# JoyDivision.net
KiCad netlist of a schematic drawn in EAGLE
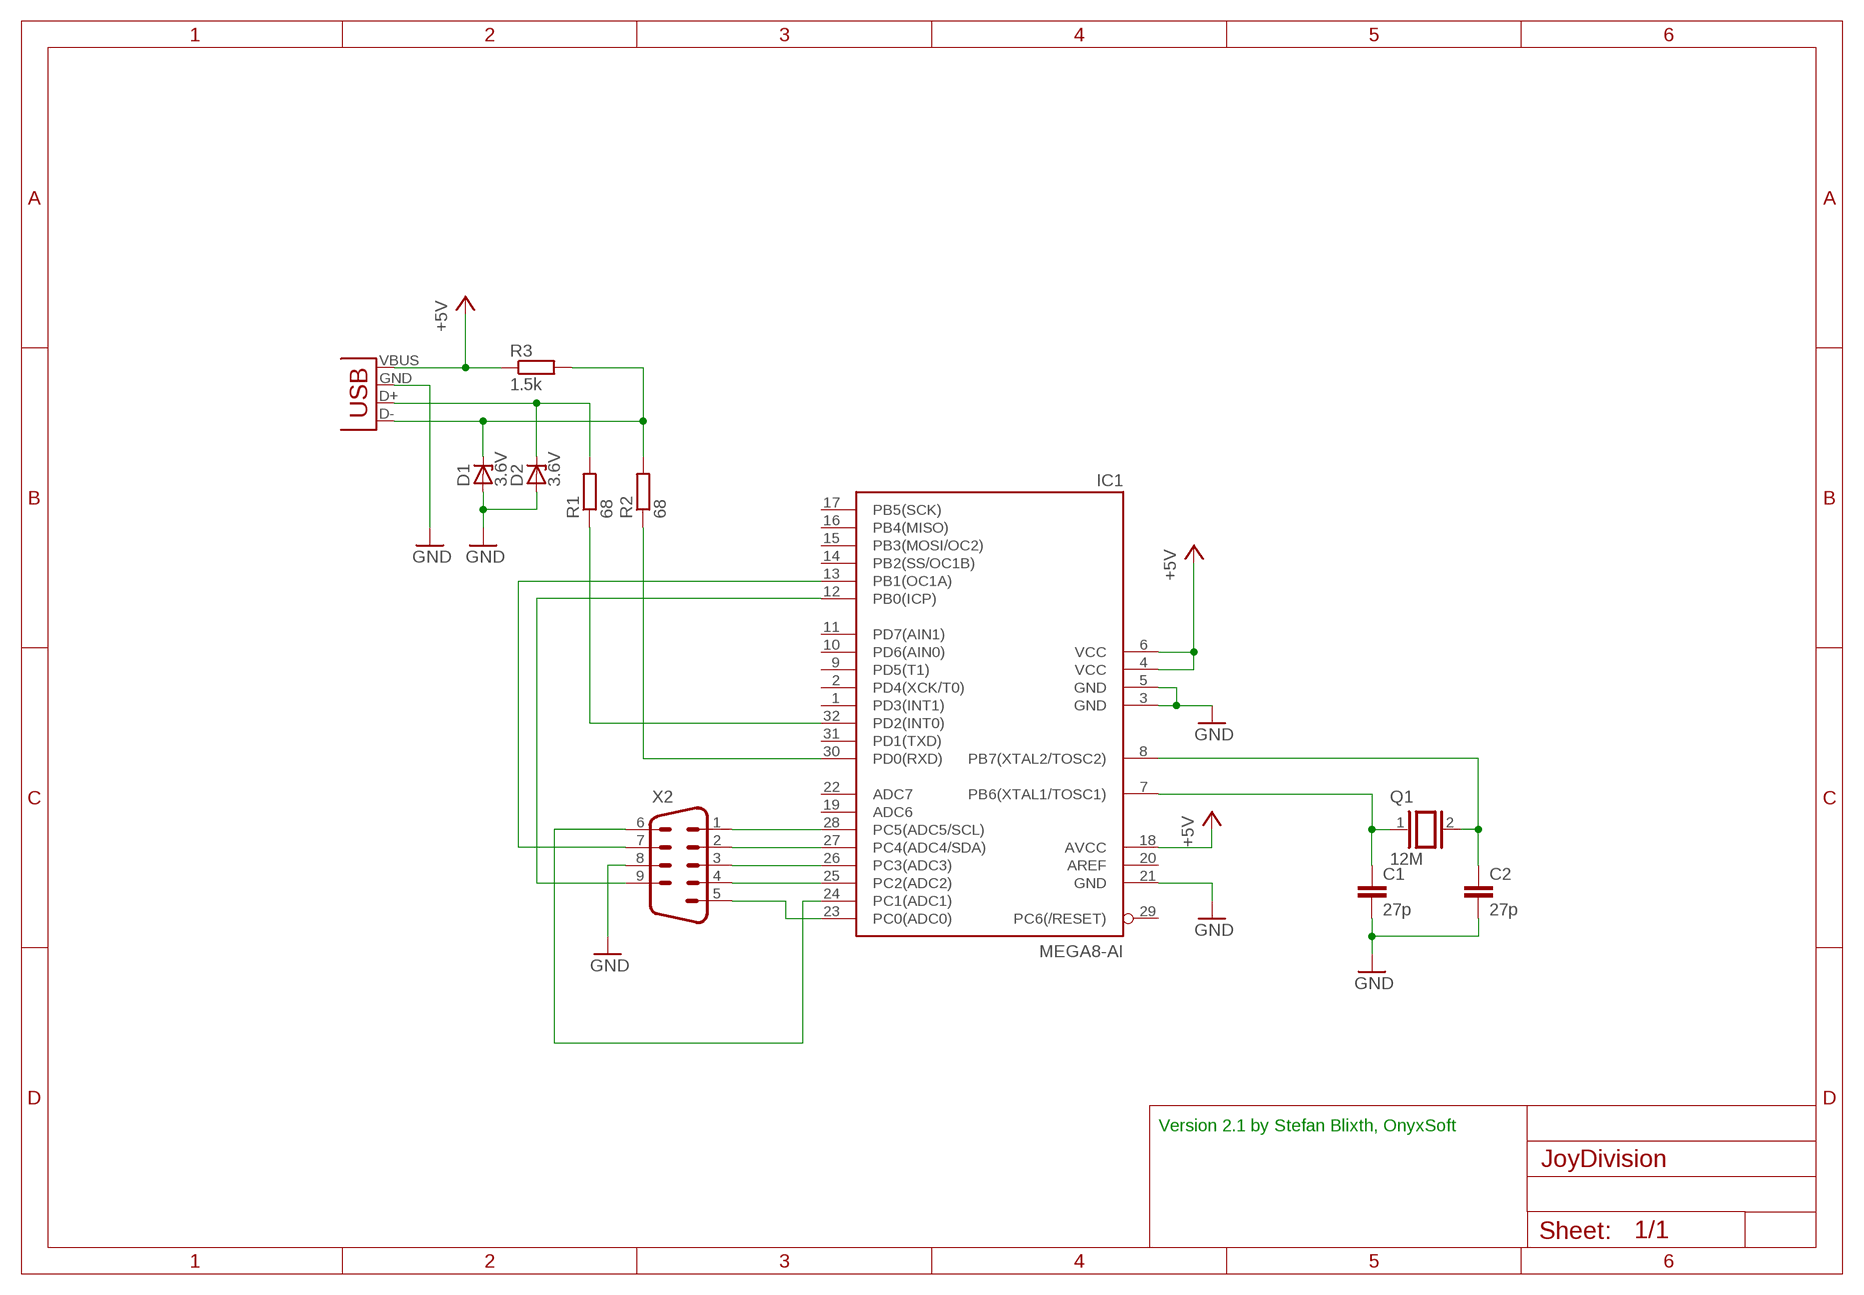
[diagram p0: schematic, sheet 1]

(export (version "E")
  (design (tool "Eeschema 10.0.6"))
  (components
    (comp (ref "C1")
      (value "27p")
      (footprint "eagle-import:C0805")
      (libsource (lib "eagle-import") (part "C-EUC0805"))
    )
    (comp (ref "C2")
      (value "27p")
      (footprint "eagle-import:C0805")
      (libsource (lib "eagle-import") (part "C-EUC0805"))
    )
    (comp (ref "D1")
      (value "3.6V")
      (footprint "eagle-import:SOD80C")
      (libsource (lib "eagle-import") (part "ZENER-DIODESOD80C"))
    )
    (comp (ref "D2")
      (value "3.6V")
      (footprint "eagle-import:SOD80C")
      (libsource (lib "eagle-import") (part "ZENER-DIODESOD80C"))
    )
    (comp (ref "IC1")
      (value "MEGA8-AI")
      (footprint "eagle-import:TQFP32-08")
      (fields (field (name "MPN") "ATMEGA8-16AU"))
      (libsource (lib "eagle-import") (part "MEGA8-AI"))
    )
    (comp (ref "JP1")
      (value "USB-A-H")
      (footprint "eagle-import:USB-A-H")
      (libsource (lib "eagle-import") (part "USB-A-H"))
    )
    (comp (ref "Q1")
      (value "12M")
      (footprint "eagle-import:QS")
      (libsource (lib "eagle-import") (part "XTAL/S"))
    )
    (comp (ref "R1")
      (value "68")
      (footprint "eagle-import:M0805")
      (libsource (lib "eagle-import") (part "R-EU_M0805"))
    )
    (comp (ref "R2")
      (value "68")
      (footprint "eagle-import:M0805")
      (libsource (lib "eagle-import") (part "R-EU_M0805"))
    )
    (comp (ref "R3")
      (value "1.5k")
      (footprint "eagle-import:M0805")
      (libsource (lib "eagle-import") (part "R-EU_M0805"))
    )
    (comp (ref "X2")
      (value "M09D")
      (footprint "eagle-import:M09D")
      (libsource (lib "eagle-import") (part "M09D"))
    )
  )
  (nets
    (net (code "1") (name "+5V") (class "Default")
      (node (ref "IC1") (pin "18") (pinfunction "AVCC_18") (pintype "power_in"))
      (node (ref "IC1") (pin "4") (pinfunction "VCC_4") (pintype "power_in"))
      (node (ref "IC1") (pin "6") (pinfunction "VCC_6") (pintype "power_in"))
      (node (ref "JP1") (pin "VBUS") (pinfunction "GND_VBUS") (pintype "bidirectional"))
      (node (ref "R3") (pin "1") (pinfunction "1_1") (pintype "passive"))
    )
    (net (code "2") (name "GND") (class "Default")
      (node (ref "C1") (pin "2") (pinfunction "2_2") (pintype "passive"))
      (node (ref "C2") (pin "2") (pinfunction "2_2") (pintype "passive"))
      (node (ref "D1") (pin "A") (pinfunction "A_A") (pintype "passive"))
      (node (ref "D2") (pin "A") (pinfunction "A_A") (pintype "passive"))
      (node (ref "IC1") (pin "21") (pinfunction "GND_21") (pintype "power_in"))
      (node (ref "IC1") (pin "3") (pinfunction "GND_3") (pintype "power_in"))
      (node (ref "IC1") (pin "5") (pinfunction "GND_5") (pintype "power_in"))
      (node (ref "JP1") (pin "GND") (pinfunction "VBUS_GND") (pintype "bidirectional"))
      (node (ref "X2") (pin "8") (pinfunction "8_8") (pintype "passive"))
    )
    (net (code "3") (name "Net-(IC1-PB0(ICP))") (class "Default")
      (node (ref "IC1") (pin "12") (pinfunction "PB0(ICP)_12") (pintype "bidirectional"))
      (node (ref "X2") (pin "9") (pinfunction "9_9") (pintype "passive"))
    )
    (net (code "4") (name "Net-(IC1-PB1(OC1A))") (class "Default")
      (node (ref "IC1") (pin "13") (pinfunction "PB1(OC1A)_13") (pintype "bidirectional"))
      (node (ref "X2") (pin "7") (pinfunction "7_7") (pintype "passive"))
    )
    (net (code "5") (name "Net-(IC1-PB6(XTAL1{slash}TOSC1))") (class "Default")
      (node (ref "C1") (pin "1") (pinfunction "1_1") (pintype "passive"))
      (node (ref "IC1") (pin "7") (pinfunction "PB6(XTAL1/TOSC1)_7") (pintype "bidirectional"))
      (node (ref "Q1") (pin "1") (pinfunction "1_1") (pintype "passive"))
    )
    (net (code "6") (name "Net-(IC1-PB7(XTAL2{slash}TOSC2))") (class "Default")
      (node (ref "C2") (pin "1") (pinfunction "1_1") (pintype "passive"))
      (node (ref "IC1") (pin "8") (pinfunction "PB7(XTAL2/TOSC2)_8") (pintype "bidirectional"))
      (node (ref "Q1") (pin "2") (pinfunction "2_2") (pintype "passive"))
    )
    (net (code "7") (name "Net-(IC1-PC0(ADC0))") (class "Default")
      (node (ref "IC1") (pin "23") (pinfunction "PC0(ADC0)_23") (pintype "bidirectional"))
      (node (ref "X2") (pin "5") (pinfunction "5_5") (pintype "passive"))
    )
    (net (code "8") (name "Net-(IC1-PC1(ADC1))") (class "Default")
      (node (ref "IC1") (pin "24") (pinfunction "PC1(ADC1)_24") (pintype "bidirectional"))
      (node (ref "X2") (pin "6") (pinfunction "6_6") (pintype "passive"))
    )
    (net (code "9") (name "Net-(IC1-PC2(ADC2))") (class "Default")
      (node (ref "IC1") (pin "25") (pinfunction "PC2(ADC2)_25") (pintype "bidirectional"))
      (node (ref "X2") (pin "4") (pinfunction "4_4") (pintype "passive"))
    )
    (net (code "10") (name "Net-(IC1-PC3(ADC3))") (class "Default")
      (node (ref "IC1") (pin "26") (pinfunction "PC3(ADC3)_26") (pintype "bidirectional"))
      (node (ref "X2") (pin "3") (pinfunction "3_3") (pintype "passive"))
    )
    (net (code "11") (name "Net-(IC1-PC4(ADC4{slash}SDA))") (class "Default")
      (node (ref "IC1") (pin "27") (pinfunction "PC4(ADC4/SDA)_27") (pintype "bidirectional"))
      (node (ref "X2") (pin "2") (pinfunction "2_2") (pintype "passive"))
    )
    (net (code "12") (name "Net-(IC1-PC5(ADC5{slash}SCL))") (class "Default")
      (node (ref "IC1") (pin "28") (pinfunction "PC5(ADC5/SCL)_28") (pintype "bidirectional"))
      (node (ref "X2") (pin "1") (pinfunction "1_1") (pintype "passive"))
    )
    (net (code "13") (name "Net-(IC1-PD0(RXD))") (class "Default")
      (node (ref "IC1") (pin "30") (pinfunction "PD0(RXD)_30") (pintype "bidirectional"))
      (node (ref "R2") (pin "1") (pinfunction "1_1") (pintype "passive"))
    )
    (net (code "14") (name "Net-(IC1-PD2(INT0))") (class "Default")
      (node (ref "IC1") (pin "32") (pinfunction "PD2(INT0)_32") (pintype "bidirectional"))
      (node (ref "R1") (pin "1") (pinfunction "1_1") (pintype "passive"))
    )
    (net (code "15") (name "Net-(JP1-D+)") (class "Default")
      (node (ref "D1") (pin "C") (pinfunction "C_C") (pintype "passive"))
      (node (ref "JP1") (pin "D-") (pinfunction "D+_D-") (pintype "bidirectional"))
      (node (ref "R2") (pin "2") (pinfunction "2_2") (pintype "passive"))
      (node (ref "R3") (pin "2") (pinfunction "2_2") (pintype "passive"))
    )
    (net (code "16") (name "Net-(JP1-D-)") (class "Default")
      (node (ref "D2") (pin "C") (pinfunction "C_C") (pintype "passive"))
      (node (ref "JP1") (pin "D+") (pinfunction "D-_D+") (pintype "bidirectional"))
      (node (ref "R1") (pin "2") (pinfunction "2_2") (pintype "passive"))
    )
    (net (code "17") (name "unconnected-(IC1-ADC6-Pad19)") (class "Default")
      (node (ref "IC1") (pin "19") (pinfunction "ADC6_19") (pintype "bidirectional"))
    )
    (net (code "18") (name "unconnected-(IC1-ADC7-Pad22)") (class "Default")
      (node (ref "IC1") (pin "22") (pinfunction "ADC7_22") (pintype "bidirectional"))
    )
    (net (code "19") (name "unconnected-(IC1-AREF-Pad20)") (class "Default")
      (node (ref "IC1") (pin "20") (pinfunction "AREF_20") (pintype "passive"))
    )
    (net (code "20") (name "unconnected-(IC1-PB2(SS{slash}OC1B)-Pad14)") (class "Default")
      (node (ref "IC1") (pin "14") (pinfunction "PB2(SS/OC1B)_14") (pintype "bidirectional"))
    )
    (net (code "21") (name "unconnected-(IC1-PB3(MOSI{slash}OC2)-Pad15)") (class "Default")
      (node (ref "IC1") (pin "15") (pinfunction "PB3(MOSI/OC2)_15") (pintype "bidirectional"))
    )
    (net (code "22") (name "unconnected-(IC1-PB4(MISO)-Pad16)") (class "Default")
      (node (ref "IC1") (pin "16") (pinfunction "PB4(MISO)_16") (pintype "bidirectional"))
    )
    (net (code "23") (name "unconnected-(IC1-PB5(SCK)-Pad17)") (class "Default")
      (node (ref "IC1") (pin "17") (pinfunction "PB5(SCK)_17") (pintype "bidirectional"))
    )
    (net (code "24") (name "unconnected-(IC1-PC6({slash}RESET)-Pad29)") (class "Default")
      (node (ref "IC1") (pin "29") (pinfunction "PC6(/RESET)_29") (pintype "bidirectional"))
    )
    (net (code "25") (name "unconnected-(IC1-PD1(TXD)-Pad31)") (class "Default")
      (node (ref "IC1") (pin "31") (pinfunction "PD1(TXD)_31") (pintype "bidirectional"))
    )
    (net (code "26") (name "unconnected-(IC1-PD3(INT1)-Pad1)") (class "Default")
      (node (ref "IC1") (pin "1") (pinfunction "PD3(INT1)_1") (pintype "bidirectional"))
    )
    (net (code "27") (name "unconnected-(IC1-PD4(XCK{slash}T0)-Pad2)") (class "Default")
      (node (ref "IC1") (pin "2") (pinfunction "PD4(XCK/T0)_2") (pintype "bidirectional"))
    )
    (net (code "28") (name "unconnected-(IC1-PD5(T1)-Pad9)") (class "Default")
      (node (ref "IC1") (pin "9") (pinfunction "PD5(T1)_9") (pintype "bidirectional"))
    )
    (net (code "29") (name "unconnected-(IC1-PD6(AIN0)-Pad10)") (class "Default")
      (node (ref "IC1") (pin "10") (pinfunction "PD6(AIN0)_10") (pintype "bidirectional"))
    )
    (net (code "30") (name "unconnected-(IC1-PD7(AIN1)-Pad11)") (class "Default")
      (node (ref "IC1") (pin "11") (pinfunction "PD7(AIN1)_11") (pintype "bidirectional"))
    )
  )
)
